# Z05_CC_SHIELD_01.net
KiCad netlist of a schematic drawn in EAGLE
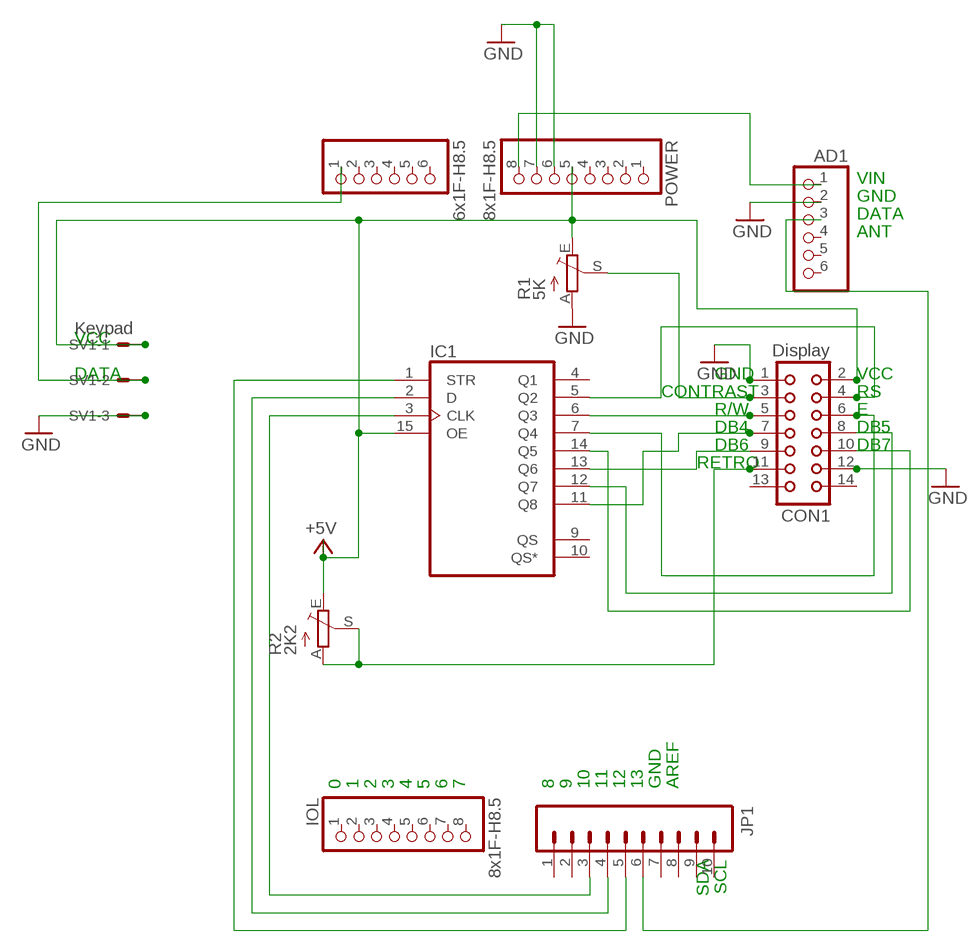
[diagram p0: schematic, sheet 1]

(export (version "E")
  (design (tool "Eeschema 10.0.6"))
  (components
    (comp (ref "AD")
      (value "6x1F-H8.5")
      (footprint "eagle-import:1X06")
      (libsource (lib "eagle-import") (part "PINHD-1X6"))
    )
    (comp (ref "AD1")
      (value "6x1F-H8.5")
      (footprint "eagle-import:1X06")
      (libsource (lib "eagle-import") (part "PINHD-1X6"))
    )
    (comp (ref "CON1")
      (value "Display")
      (footprint "eagle-import:CON14")
      (libsource (lib "eagle-import") (part "CON14"))
    )
    (comp (ref "IC1")
      (value "4094N")
      (footprint "eagle-import:DIL16")
      (libsource (lib "eagle-import") (part "4094N"))
    )
    (comp (ref "IOL")
      (value "8x1F-H8.5")
      (footprint "eagle-import:1X08")
      (libsource (lib "eagle-import") (part "PINHD-1X8"))
    )
    (comp (ref "JP1")
      (value "M10\"")
      (footprint "eagle-import:1X10")
      (libsource (lib "eagle-import") (part "M10{dblquote}"))
    )
    (comp (ref "POWER")
      (value "8x1F-H8.5")
      (footprint "eagle-import:1X08")
      (libsource (lib "eagle-import") (part "PINHD-1X8"))
    )
    (comp (ref "R1")
      (value "5K")
      (footprint "eagle-import:LI10")
      (libsource (lib "eagle-import") (part "TRIM_EU-LI10"))
    )
    (comp (ref "R2")
      (value "2K2")
      (footprint "eagle-import:LI10")
      (libsource (lib "eagle-import") (part "TRIM_EU-LI10"))
    )
    (comp (ref "SV1")
      (value "Keypad")
      (footprint "eagle-import:7395-05")
      (libsource (lib "eagle-import") (part "22-?-0505-7058"))
    )
  )
  (nets
    (net (code "1") (name "+5V") (class "Default")
      (node (ref "CON1") (pin "2") (pinfunction "2_2") (pintype "passive"))
      (node (ref "IC1") (pin "15") (pinfunction "OE_15") (pintype "input"))
      (node (ref "POWER") (pin "5") (pinfunction "5_5") (pintype "passive"))
      (node (ref "R1") (pin "E") (pinfunction "E_E") (pintype "passive"))
      (node (ref "R2") (pin "E") (pinfunction "E_E") (pintype "passive"))
      (node (ref "SV1") (pin "1") (pinfunction "S_1") (pintype "passive"))
    )
    (net (code "2") (name "GND") (class "Default")
      (node (ref "AD1") (pin "2") (pinfunction "2_2") (pintype "passive"))
      (node (ref "CON1") (pin "1") (pinfunction "1_1") (pintype "passive"))
      (node (ref "CON1") (pin "12") (pinfunction "12_12") (pintype "passive"))
      (node (ref "POWER") (pin "6") (pinfunction "6_6") (pintype "passive"))
      (node (ref "POWER") (pin "7") (pinfunction "7_7") (pintype "passive"))
      (node (ref "R1") (pin "A") (pinfunction "A_A") (pintype "passive"))
      (node (ref "SV1") (pin "3") (pinfunction "S_3") (pintype "passive"))
    )
    (net (code "3") (name "Net-(AD1-Pad1)") (class "Default")
      (node (ref "AD1") (pin "1") (pinfunction "1_1") (pintype "passive"))
      (node (ref "POWER") (pin "8") (pinfunction "8_8") (pintype "passive"))
    )
    (net (code "4") (name "Net-(AD1-Pad3)") (class "Default")
      (node (ref "AD1") (pin "3") (pinfunction "3_3") (pintype "passive"))
      (node (ref "JP1") (pin "6") (pinfunction "6_6") (pintype "passive"))
    )
    (net (code "5") (name "Net-(CON1-Pad3)") (class "Default")
      (node (ref "CON1") (pin "3") (pinfunction "3_3") (pintype "passive"))
      (node (ref "R1") (pin "S") (pinfunction "S_S") (pintype "passive"))
    )
    (net (code "6") (name "Net-(CON1-Pad11)") (class "Default")
      (node (ref "CON1") (pin "11") (pinfunction "11_11") (pintype "passive"))
      (node (ref "R2") (pin "A") (pinfunction "A_A") (pintype "passive"))
      (node (ref "R2") (pin "S") (pinfunction "S_S") (pintype "passive"))
    )
    (net (code "7") (name "Net-(IC1A-CLK)") (class "Default")
      (node (ref "IC1") (pin "3") (pinfunction "CLK_3") (pintype "input"))
      (node (ref "JP1") (pin "3") (pinfunction "3_3") (pintype "passive"))
    )
    (net (code "8") (name "Net-(IC1A-D)") (class "Default")
      (node (ref "IC1") (pin "2") (pinfunction "D_2") (pintype "input"))
      (node (ref "JP1") (pin "4") (pinfunction "4_4") (pintype "passive"))
    )
    (net (code "9") (name "Net-(IC1A-Q2)") (class "Default")
      (node (ref "CON1") (pin "4") (pinfunction "4_4") (pintype "passive"))
      (node (ref "IC1") (pin "5") (pinfunction "Q2_5") (pintype "output"))
    )
    (net (code "10") (name "Net-(IC1A-Q3)") (class "Default")
      (node (ref "CON1") (pin "5") (pinfunction "5_5") (pintype "passive"))
      (node (ref "IC1") (pin "6") (pinfunction "Q3_6") (pintype "output"))
    )
    (net (code "11") (name "Net-(IC1A-Q4)") (class "Default")
      (node (ref "CON1") (pin "6") (pinfunction "6_6") (pintype "passive"))
      (node (ref "IC1") (pin "7") (pinfunction "Q4_7") (pintype "output"))
    )
    (net (code "12") (name "Net-(IC1A-Q5)") (class "Default")
      (node (ref "CON1") (pin "10") (pinfunction "10_10") (pintype "passive"))
      (node (ref "IC1") (pin "14") (pinfunction "Q5_14") (pintype "output"))
    )
    (net (code "13") (name "Net-(IC1A-Q6)") (class "Default")
      (node (ref "CON1") (pin "9") (pinfunction "9_9") (pintype "passive"))
      (node (ref "IC1") (pin "13") (pinfunction "Q6_13") (pintype "output"))
    )
    (net (code "14") (name "Net-(IC1A-Q7)") (class "Default")
      (node (ref "CON1") (pin "8") (pinfunction "8_8") (pintype "passive"))
      (node (ref "IC1") (pin "12") (pinfunction "Q7_12") (pintype "output"))
    )
    (net (code "15") (name "Net-(IC1A-Q8)") (class "Default")
      (node (ref "CON1") (pin "7") (pinfunction "7_7") (pintype "passive"))
      (node (ref "IC1") (pin "11") (pinfunction "Q8_11") (pintype "output"))
    )
    (net (code "16") (name "Net-(IC1A-STR)") (class "Default")
      (node (ref "IC1") (pin "1") (pinfunction "STR_1") (pintype "input"))
      (node (ref "JP1") (pin "5") (pinfunction "5_5") (pintype "passive"))
    )
    (net (code "17") (name "Net-(SV1B-S)") (class "Default")
      (node (ref "AD") (pin "1") (pinfunction "1_1") (pintype "passive"))
      (node (ref "SV1") (pin "2") (pinfunction "S_2") (pintype "passive"))
    )
    (net (code "18") (name "unconnected-(AD-Pad2)") (class "Default")
      (node (ref "AD") (pin "2") (pinfunction "2_2") (pintype "passive"))
    )
    (net (code "19") (name "unconnected-(AD-Pad3)") (class "Default")
      (node (ref "AD") (pin "3") (pinfunction "3_3") (pintype "passive"))
    )
    (net (code "20") (name "unconnected-(AD-Pad4)") (class "Default")
      (node (ref "AD") (pin "4") (pinfunction "4_4") (pintype "passive"))
    )
    (net (code "21") (name "unconnected-(AD-Pad5)") (class "Default")
      (node (ref "AD") (pin "5") (pinfunction "5_5") (pintype "passive"))
    )
    (net (code "22") (name "unconnected-(AD-Pad6)") (class "Default")
      (node (ref "AD") (pin "6") (pinfunction "6_6") (pintype "passive"))
    )
    (net (code "23") (name "unconnected-(AD1-Pad4)") (class "Default")
      (node (ref "AD1") (pin "4") (pinfunction "4_4") (pintype "passive"))
    )
    (net (code "24") (name "unconnected-(AD1-Pad5)") (class "Default")
      (node (ref "AD1") (pin "5") (pinfunction "5_5") (pintype "passive"))
    )
    (net (code "25") (name "unconnected-(AD1-Pad6)") (class "Default")
      (node (ref "AD1") (pin "6") (pinfunction "6_6") (pintype "passive"))
    )
    (net (code "26") (name "unconnected-(CON1-Pad13)") (class "Default")
      (node (ref "CON1") (pin "13") (pinfunction "13_13") (pintype "passive"))
    )
    (net (code "27") (name "unconnected-(CON1-Pad14)") (class "Default")
      (node (ref "CON1") (pin "14") (pinfunction "14_14") (pintype "passive"))
    )
    (net (code "28") (name "unconnected-(IC1A-Q1-Pad4)") (class "Default")
      (node (ref "IC1") (pin "4") (pinfunction "Q1_4") (pintype "output"))
    )
    (net (code "29") (name "unconnected-(IC1A-QS*-Pad10)") (class "Default")
      (node (ref "IC1") (pin "10") (pinfunction "QS*_10") (pintype "output"))
    )
    (net (code "30") (name "unconnected-(IC1A-QS-Pad9)") (class "Default")
      (node (ref "IC1") (pin "9") (pinfunction "QS_9") (pintype "output"))
    )
    (net (code "31") (name "unconnected-(IOL-Pad1)") (class "Default")
      (node (ref "IOL") (pin "1") (pinfunction "1_1") (pintype "passive"))
    )
    (net (code "32") (name "unconnected-(IOL-Pad2)") (class "Default")
      (node (ref "IOL") (pin "2") (pinfunction "2_2") (pintype "passive"))
    )
    (net (code "33") (name "unconnected-(IOL-Pad3)") (class "Default")
      (node (ref "IOL") (pin "3") (pinfunction "3_3") (pintype "passive"))
    )
    (net (code "34") (name "unconnected-(IOL-Pad4)") (class "Default")
      (node (ref "IOL") (pin "4") (pinfunction "4_4") (pintype "passive"))
    )
    (net (code "35") (name "unconnected-(IOL-Pad5)") (class "Default")
      (node (ref "IOL") (pin "5") (pinfunction "5_5") (pintype "passive"))
    )
    (net (code "36") (name "unconnected-(IOL-Pad6)") (class "Default")
      (node (ref "IOL") (pin "6") (pinfunction "6_6") (pintype "passive"))
    )
    (net (code "37") (name "unconnected-(IOL-Pad7)") (class "Default")
      (node (ref "IOL") (pin "7") (pinfunction "7_7") (pintype "passive"))
    )
    (net (code "38") (name "unconnected-(IOL-Pad8)") (class "Default")
      (node (ref "IOL") (pin "8") (pinfunction "8_8") (pintype "passive"))
    )
    (net (code "39") (name "unconnected-(JP1-Pad1)") (class "Default")
      (node (ref "JP1") (pin "1") (pinfunction "1_1") (pintype "passive"))
    )
    (net (code "40") (name "unconnected-(JP1-Pad2)") (class "Default")
      (node (ref "JP1") (pin "2") (pinfunction "2_2") (pintype "passive"))
    )
    (net (code "41") (name "unconnected-(JP1-Pad7)") (class "Default")
      (node (ref "JP1") (pin "7") (pinfunction "7_7") (pintype "passive"))
    )
    (net (code "42") (name "unconnected-(JP1-Pad8)") (class "Default")
      (node (ref "JP1") (pin "8") (pinfunction "8_8") (pintype "passive"))
    )
    (net (code "43") (name "unconnected-(JP1-Pad9)") (class "Default")
      (node (ref "JP1") (pin "9") (pinfunction "9_9") (pintype "passive"))
    )
    (net (code "44") (name "unconnected-(JP1-Pad10)") (class "Default")
      (node (ref "JP1") (pin "10") (pinfunction "10_10") (pintype "passive"))
    )
    (net (code "45") (name "unconnected-(POWER-Pad1)") (class "Default")
      (node (ref "POWER") (pin "1") (pinfunction "1_1") (pintype "passive"))
    )
    (net (code "46") (name "unconnected-(POWER-Pad2)") (class "Default")
      (node (ref "POWER") (pin "2") (pinfunction "2_2") (pintype "passive"))
    )
    (net (code "47") (name "unconnected-(POWER-Pad3)") (class "Default")
      (node (ref "POWER") (pin "3") (pinfunction "3_3") (pintype "passive"))
    )
    (net (code "48") (name "unconnected-(POWER-Pad4)") (class "Default")
      (node (ref "POWER") (pin "4") (pinfunction "4_4") (pintype "passive"))
    )
  )
)
